# 5_Teensy.net
KiCad netlist of a schematic drawn in Altium Designer
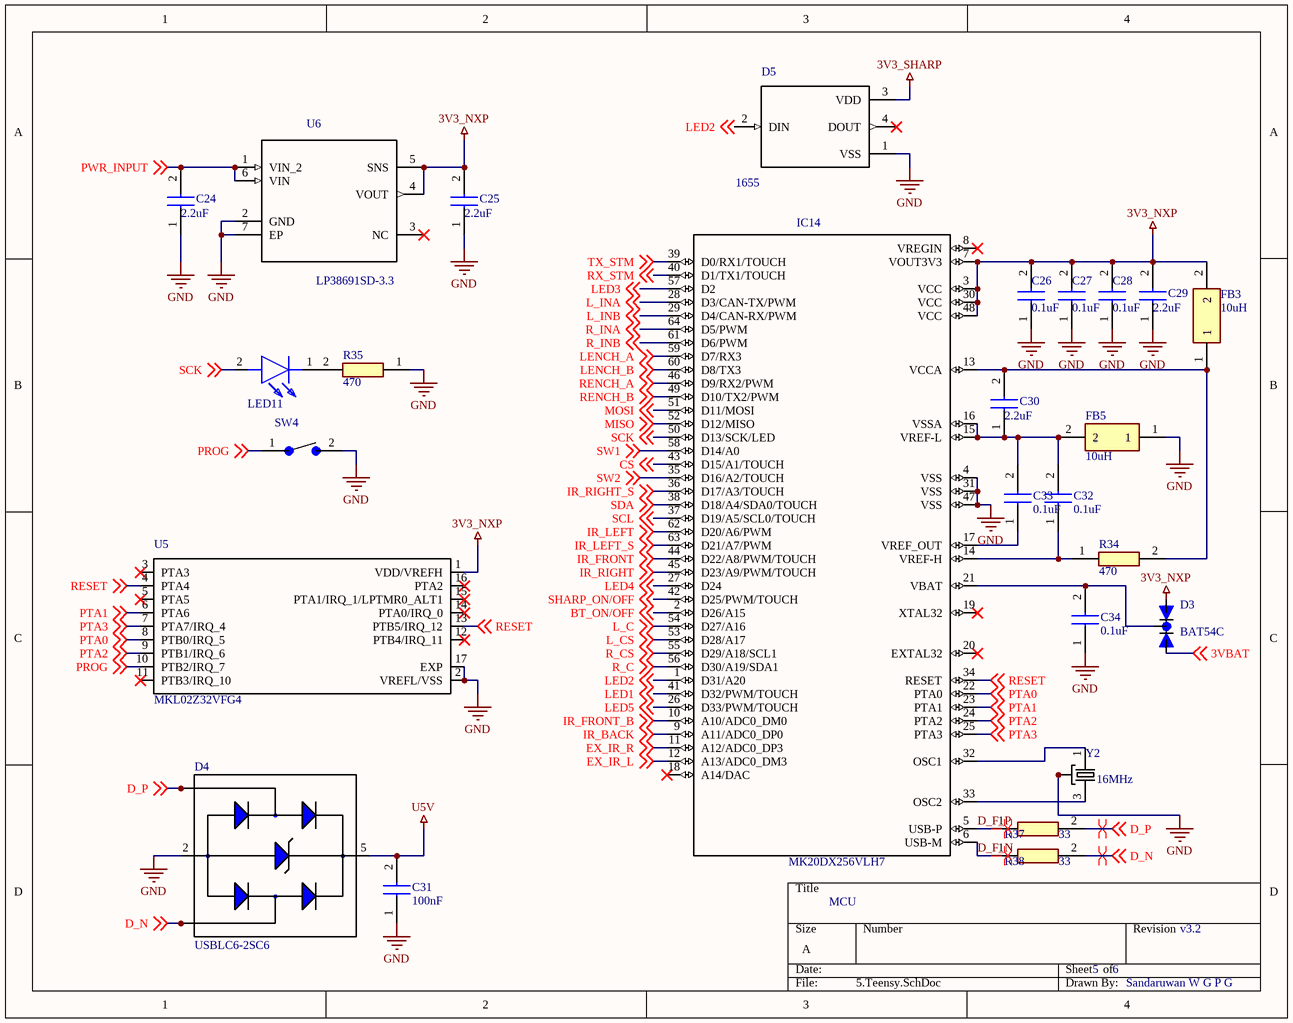
[diagram p0: 5.Teensy.SchDoc]

(export (version "E")
  (design (tool "Eeschema 10.0.6"))
  (components
    (comp (ref "C24")
      (value "2.2uF")
      (footprint "CAPC2012X94N")
      (description "Capacitor")
      (fields
        (field (name "MANUFACTURER_PART_NUMBER") "08055A101JAT2A")
        (field (name "MOUSER PART NUMBER") "581-08055A101J")
      )
      (libsource (lib "micromouse library") (part "08055A101JAT2A"))
    )
    (comp (ref "C25")
      (value "2.2uF")
      (footprint "CAPC2012X94N")
      (description "Capacitor")
      (fields
        (field (name "MANUFACTURER_PART_NUMBER") "08055A101JAT2A")
        (field (name "MOUSER PART NUMBER") "581-08055A101J")
      )
      (libsource (lib "micromouse library") (part "08055A101JAT2A"))
    )
    (comp (ref "C26")
      (value "0.1uF")
      (footprint "*CAPC1608X95N")
      (description "Capacitor")
      (fields (field (name "Comment") "capacitor 0603"))
      (libsource (lib "micromouse library") (part "capacitor 0603"))
    )
    (comp (ref "C27")
      (value "0.1uF")
      (footprint "*CAPC1608X95N")
      (description "Capacitor")
      (fields (field (name "Comment") "capacitor 0603"))
      (libsource (lib "micromouse library") (part "capacitor 0603"))
    )
    (comp (ref "C28")
      (value "0.1uF")
      (footprint "*CAPC1608X95N")
      (description "Capacitor")
      (fields (field (name "Comment") "capacitor 0603"))
      (libsource (lib "micromouse library") (part "capacitor 0603"))
    )
    (comp (ref "C29")
      (value "2.2uF")
      (footprint "CAPC2012X94N")
      (description "Capacitor")
      (fields
        (field (name "MANUFACTURER_PART_NUMBER") "08055A101JAT2A")
        (field (name "MOUSER PART NUMBER") "581-08055A101J")
      )
      (libsource (lib "micromouse library") (part "08055A101JAT2A"))
    )
    (comp (ref "C30")
      (value "2.2uF")
      (footprint "CAPC2012X94N")
      (description "Capacitor")
      (fields
        (field (name "MANUFACTURER_PART_NUMBER") "08055A101JAT2A")
        (field (name "MOUSER PART NUMBER") "581-08055A101J")
      )
      (libsource (lib "micromouse library") (part "08055A101JAT2A"))
    )
    (comp (ref "C31")
      (value "100nF")
      (footprint "*CAPC1608X95N")
      (description "Capacitor")
      (fields (field (name "Comment") "capacitor 0603"))
      (libsource (lib "micromouse library") (part "capacitor 0603"))
    )
    (comp (ref "C32")
      (value "0.1uF")
      (footprint "*CAPC1608X95N")
      (description "Capacitor")
      (fields (field (name "Comment") "capacitor 0603"))
      (libsource (lib "micromouse library") (part "capacitor 0603"))
    )
    (comp (ref "C33")
      (value "0.1uF")
      (footprint "*CAPC1608X95N")
      (description "Capacitor")
      (fields (field (name "Comment") "capacitor 0603"))
      (libsource (lib "micromouse library") (part "capacitor 0603"))
    )
    (comp (ref "C34")
      (value "0.1uF")
      (footprint "*CAPC1608X95N")
      (description "Capacitor")
      (fields (field (name "Comment") "capacitor 0603"))
      (libsource (lib "micromouse library") (part "capacitor 0603"))
    )
    (comp (ref "D3")
      (value "BAT54C")
      (footprint "*SOT23-R")
      (fields (field (name "MF") "ON Semiconductor"))
      (libsource (lib "micromouse library") (part "BAT54C"))
    )
    (comp (ref "D4")
      (value "USBLC6-2SC6")
      (footprint "*SOT95P280X145-6N")
      (description "USBLC6 Series 2 Line 6 V Uni / Bi-Directional ESD Protection - SOT-23-6")
      (fields (field (name "MF") "STMicroelectronics"))
      (libsource (lib "micromouse library") (part "USBLC6-2SC6"))
    )
    (comp (ref "D5")
      (value "1655")
      (footprint "*LED_1655")
      (fields (field (name "DIGI-KEY_PART_NUMBER") "1528-1104-ND") (field (name "MF") "Adafruit"))
      (libsource (lib "micromouse library") (part "1655"))
    )
    (comp (ref "FB3")
      (value "10uH")
      (footprint "BEADC1608X95N")
      (description "Ferrite Bead")
      (fields (field (name "Comment") "inductor 0603"))
      (libsource (lib "") (part "inductor 0603_1"))
    )
    (comp (ref "FB5")
      (value "10uH")
      (footprint "BEADC1608X95N")
      (description "Ferrite Bead")
      (fields (field (name "Comment") "inductor 0603"))
      (libsource (lib "micromouse library") (part "inductor 0603"))
    )
    (comp (ref "IC14")
      (value "MK20DX256VLH7")
      (footprint "QFP50P1200X1200X160-64N")
      (description "Kinetis K20: 72MHz Cortex-M4 Performance MCU, 288KB Flash, 64KB SRAM, Full-Speed USB, 64-LQFP")
      (fields (field (name "MF") "NXP USA"))
      (libsource (lib "micromouse library") (part "MK20DX256VLH7_1"))
    )
    (comp (ref "LED11")
      (value "150080BS75000")
      (footprint "LEDC2012X80N")
      (description "LED")
      (fields
        (field (name "MOUSER PART NUMBER") "710-150080BS75000")
        (field (name "RS PART NUMBER") "8154228P")
      )
      (libsource (lib "micromouse library") (part "150080BS75000"))
    )
    (comp (ref "R34")
      (value "470")
      (footprint "RESC1608X55N")
      (description "Resistor")
      (fields (field (name "Comment") "resistor"))
      (libsource (lib "micromouse library") (part "resistor"))
    )
    (comp (ref "R35")
      (value "470")
      (footprint "RESC1608X55N")
      (description "Resistor")
      (fields (field (name "Comment") "resistor"))
      (libsource (lib "") (part "resistor_1"))
    )
    (comp (ref "R37")
      (value "33")
      (footprint "RESC1608X55N")
      (description "Resistor")
      (fields (field (name "Comment") "resistor"))
      (libsource (lib "micromouse library") (part "resistor"))
    )
    (comp (ref "R38")
      (value "33")
      (footprint "RESC1608X55N")
      (description "Resistor")
      (fields (field (name "Comment") "resistor"))
      (libsource (lib "micromouse library") (part "resistor"))
    )
    (comp (ref "SW4")
      (value "1437566-3")
      (footprint "*TE_FSMSM")
      (description "Switch Tactile OFF _ON_ SPST Rectangular Button Gull Wing 0.05A 12VDC SMD Loose Piece")
      (fields (field (name "MF") "TE Connectivity") (field (name "MP") "FSMSM"))
      (libsource (lib "micromouse library") (part "FSMSM"))
    )
    (comp (ref "U5")
      (value "MKL02Z32VFG4")
      (footprint "*QFN50P300X300X65-17N")
      (description "32 Bit Microcontroller, Kinetis L Series Ultra Low Power, ARM Cortex-M0+, 48 MHz, 32 KB, 4 KB, 16")
      (fields (field (name "MF") "NXP USA"))
      (libsource (lib "micromouse library") (part "MKL02Z32VFG4_1"))
    )
    (comp (ref "U6")
      (value "LP38691SD-3.3")
      (footprint "*DFN300X300X80-7N")
      (description "500mA Low Dropout CMOS Linear Regulators Stable with Ceramic Output Capacitors 6-WSON -40 to 125")
      (fields (field (name "MF") "Texas Instruments"))
      (libsource (lib "micromouse library") (part "LP38691SD-3.3"))
    )
    (comp (ref "Y2")
      (value "16MHz")
      (footprint "*OSCCC320X250X60N")
      (description "Crystal 12.0000mhz 8pf Smd")
      (fields (field (name "MP") "NX3225SA-12.000M-STD-CRS-2") (field (name "MF") "NDK America,"))
      (libsource (lib "micromouse library") (part "NX3225SA-12.000M-STD-CRS-2"))
    )
  )
  (nets
    (net (code "1") (name "/D_F_N") (class "Default")
      (node (ref "IC14") (pin "6") (pinfunction "USB-M_6") (pintype "bidirectional"))
      (node (ref "R38") (pin "1") (pinfunction "1_1") (pintype "passive"))
    )
    (net (code "2") (name "/D_F_P") (class "Default")
      (node (ref "IC14") (pin "5") (pinfunction "USB-P_5") (pintype "bidirectional"))
      (node (ref "R37") (pin "1") (pinfunction "1_1") (pintype "passive"))
    )
    (net (code "3") (name "3V3_NXP") (class "Default")
      (node (ref "C25") (pin "2") (pinfunction "2_2") (pintype "passive"))
      (node (ref "C26") (pin "2") (pinfunction "2_2") (pintype "passive"))
      (node (ref "C27") (pin "2") (pinfunction "2_2") (pintype "passive"))
      (node (ref "C28") (pin "2") (pinfunction "2_2") (pintype "passive"))
      (node (ref "C29") (pin "2") (pinfunction "2_2") (pintype "passive"))
      (node (ref "D3") (pin "2") (pinfunction "A2_2") (pintype "passive"))
      (node (ref "FB3") (pin "2") (pinfunction "2_2") (pintype "passive"))
      (node (ref "IC14") (pin "3") (pinfunction "VCC_3") (pintype "bidirectional"))
      (node (ref "IC14") (pin "30") (pinfunction "VCC_30") (pintype "bidirectional"))
      (node (ref "IC14") (pin "48") (pinfunction "VCC_48") (pintype "bidirectional"))
      (node (ref "IC14") (pin "7") (pinfunction "VOUT3V3_7") (pintype "bidirectional"))
      (node (ref "U5") (pin "1") (pinfunction "VDD/VREFH_1") (pintype "power_in"))
      (node (ref "U6") (pin "4") (pinfunction "VOUT_4") (pintype "output"))
      (node (ref "U6") (pin "5") (pinfunction "SNS_5") (pintype "passive"))
    )
    (net (code "4") (name "3V3_SHARP") (class "Default")
      (node (ref "D5") (pin "3") (pinfunction "VDD_3") (pintype "power_in"))
    )
    (net (code "5") (name "3VBAT") (class "Default")
      (node (ref "D3") (pin "1") (pinfunction "A1_1") (pintype "passive"))
    )
    (net (code "6") (name "BT_ON{slash}OFF") (class "Default")
      (node (ref "IC14") (pin "2") (pinfunction "D26/A15_2") (pintype "bidirectional"))
    )
    (net (code "7") (name "CS") (class "Default")
      (node (ref "IC14") (pin "43") (pinfunction "D15/A1/TOUCH_43") (pintype "bidirectional"))
    )
    (net (code "8") (name "D_N") (class "Default")
      (node (ref "D4") (pin "3") (pinfunction "I/O2_3") (pintype "bidirectional"))
      (node (ref "D4") (pin "4") (pinfunction "I/O2_4") (pintype "bidirectional"))
      (node (ref "R38") (pin "2") (pinfunction "2_2") (pintype "passive"))
    )
    (net (code "9") (name "D_P") (class "Default")
      (node (ref "D4") (pin "1") (pinfunction "I/O1_1") (pintype "bidirectional"))
      (node (ref "D4") (pin "6") (pinfunction "I/O1_6") (pintype "bidirectional"))
      (node (ref "R37") (pin "2") (pinfunction "2_2") (pintype "passive"))
    )
    (net (code "10") (name "EX_IR_L") (class "Default")
      (node (ref "IC14") (pin "12") (pinfunction "A13/ADC0_DM3_12") (pintype "bidirectional"))
    )
    (net (code "11") (name "EX_IR_R") (class "Default")
      (node (ref "IC14") (pin "11") (pinfunction "A12/ADC0_DP3_11") (pintype "bidirectional"))
    )
    (net (code "12") (name "GND") (class "Default")
      (node (ref "C24") (pin "1") (pinfunction "1_1") (pintype "passive"))
      (node (ref "C25") (pin "1") (pinfunction "1_1") (pintype "passive"))
      (node (ref "C26") (pin "1") (pinfunction "1_1") (pintype "passive"))
      (node (ref "C27") (pin "1") (pinfunction "1_1") (pintype "passive"))
      (node (ref "C28") (pin "1") (pinfunction "1_1") (pintype "passive"))
      (node (ref "C29") (pin "1") (pinfunction "1_1") (pintype "passive"))
      (node (ref "C31") (pin "1") (pinfunction "1_1") (pintype "passive"))
      (node (ref "C34") (pin "1") (pinfunction "1_1") (pintype "passive"))
      (node (ref "D4") (pin "2") (pinfunction "GND_2") (pintype "power_in"))
      (node (ref "D5") (pin "1") (pinfunction "VSS_1") (pintype "power_in"))
      (node (ref "FB5") (pin "1") (pinfunction "1_1") (pintype "passive"))
      (node (ref "IC14") (pin "31") (pinfunction "VSS_31") (pintype "bidirectional"))
      (node (ref "IC14") (pin "4") (pinfunction "VSS_4") (pintype "bidirectional"))
      (node (ref "IC14") (pin "47") (pinfunction "VSS_47") (pintype "bidirectional"))
      (node (ref "R35") (pin "1") (pinfunction "1_1") (pintype "passive"))
      (node (ref "SW4") (pin "2") (pinfunction "2_2") (pintype "passive"))
      (node (ref "U5") (pin "17") (pinfunction "EXP_17") (pintype "power_in"))
      (node (ref "U5") (pin "2") (pinfunction "VREFL/VSS_2") (pintype "power_in"))
      (node (ref "U6") (pin "2") (pinfunction "GND_2") (pintype "passive"))
      (node (ref "U6") (pin "7") (pinfunction "EP_7") (pintype "passive"))
      (node (ref "Y2") (pin "2") (pinfunction "GND_2") (pintype "passive"))
      (node (ref "Y2") (pin "4") (pinfunction "GND_4") (pintype "passive"))
    )
    (net (code "13") (name "IR_BACK") (class "Default")
      (node (ref "IC14") (pin "9") (pinfunction "A11/ADC0_DP0_9") (pintype "bidirectional"))
    )
    (net (code "14") (name "IR_FRONT") (class "Default")
      (node (ref "IC14") (pin "44") (pinfunction "D22/A8/PWM/TOUCH_44") (pintype "bidirectional"))
    )
    (net (code "15") (name "IR_FRONT_B") (class "Default")
      (node (ref "IC14") (pin "10") (pinfunction "A10/ADC0_DM0_10") (pintype "bidirectional"))
    )
    (net (code "16") (name "IR_LEFT") (class "Default")
      (node (ref "IC14") (pin "62") (pinfunction "D20/A6/PWM_62") (pintype "bidirectional"))
    )
    (net (code "17") (name "IR_LEFT_S") (class "Default")
      (node (ref "IC14") (pin "63") (pinfunction "D21/A7/PWM_63") (pintype "bidirectional"))
    )
    (net (code "18") (name "IR_RIGHT") (class "Default")
      (node (ref "IC14") (pin "45") (pinfunction "D23/A9/PWM/TOUCH_45") (pintype "bidirectional"))
    )
    (net (code "19") (name "IR_RIGHT_S") (class "Default")
      (node (ref "IC14") (pin "36") (pinfunction "D17/A3/TOUCH_36") (pintype "bidirectional"))
    )
    (net (code "20") (name "LED1") (class "Default")
      (node (ref "IC14") (pin "41") (pinfunction "D32/PWM/TOUCH_41") (pintype "bidirectional"))
    )
    (net (code "21") (name "LED2") (class "Default")
      (node (ref "D5") (pin "2") (pinfunction "DIN_2") (pintype "input"))
      (node (ref "IC14") (pin "1") (pinfunction "D31/A20_1") (pintype "bidirectional"))
    )
    (net (code "22") (name "LED3") (class "Default")
      (node (ref "IC14") (pin "57") (pinfunction "D2_57") (pintype "bidirectional"))
    )
    (net (code "23") (name "LED4") (class "Default")
      (node (ref "IC14") (pin "27") (pinfunction "D24_27") (pintype "bidirectional"))
    )
    (net (code "24") (name "LED5") (class "Default")
      (node (ref "IC14") (pin "26") (pinfunction "D33/PWM/TOUCH_26") (pintype "bidirectional"))
    )
    (net (code "25") (name "LENCH_A") (class "Default")
      (node (ref "IC14") (pin "59") (pinfunction "D7/RX3_59") (pintype "bidirectional"))
    )
    (net (code "26") (name "LENCH_B") (class "Default")
      (node (ref "IC14") (pin "60") (pinfunction "D8/TX3_60") (pintype "bidirectional"))
    )
    (net (code "27") (name "L_C") (class "Default")
      (node (ref "IC14") (pin "54") (pinfunction "D27/A16_54") (pintype "bidirectional"))
    )
    (net (code "28") (name "L_CS") (class "Default")
      (node (ref "IC14") (pin "53") (pinfunction "D28/A17_53") (pintype "bidirectional"))
    )
    (net (code "29") (name "L_INA") (class "Default")
      (node (ref "IC14") (pin "28") (pinfunction "D3/CAN-TX/PWM_28") (pintype "bidirectional"))
    )
    (net (code "30") (name "L_INB") (class "Default")
      (node (ref "IC14") (pin "29") (pinfunction "D4/CAN-RX/PWM_29") (pintype "bidirectional"))
    )
    (net (code "31") (name "MISO") (class "Default")
      (node (ref "IC14") (pin "52") (pinfunction "D12/MISO_52") (pintype "bidirectional"))
    )
    (net (code "32") (name "MOSI") (class "Default")
      (node (ref "IC14") (pin "51") (pinfunction "D11/MOSI_51") (pintype "bidirectional"))
    )
    (net (code "33") (name "Net-(D3-C)") (class "Default")
      (node (ref "C34") (pin "2") (pinfunction "2_2") (pintype "passive"))
      (node (ref "D3") (pin "3") (pinfunction "C_3") (pintype "passive"))
      (node (ref "IC14") (pin "21") (pinfunction "VBAT_21") (pintype "bidirectional"))
    )
    (net (code "34") (name "Net-(IC14-OSC1)") (class "Default")
      (node (ref "IC14") (pin "32") (pinfunction "OSC1_32") (pintype "bidirectional"))
      (node (ref "Y2") (pin "1") (pinfunction "1_1") (pintype "passive"))
    )
    (net (code "35") (name "Net-(IC14-OSC2)") (class "Default")
      (node (ref "IC14") (pin "33") (pinfunction "OSC2_33") (pintype "bidirectional"))
      (node (ref "Y2") (pin "3") (pinfunction "3_3") (pintype "passive"))
    )
    (net (code "36") (name "Net-(IC14-VCCA)") (class "Default")
      (node (ref "C30") (pin "2") (pinfunction "2_2") (pintype "passive"))
      (node (ref "FB3") (pin "1") (pinfunction "1_1") (pintype "passive"))
      (node (ref "IC14") (pin "13") (pinfunction "VCCA_13") (pintype "bidirectional"))
      (node (ref "R34") (pin "2") (pinfunction "2_2") (pintype "passive"))
    )
    (net (code "37") (name "Net-(IC14-VREF-H)") (class "Default")
      (node (ref "C32") (pin "1") (pinfunction "1_1") (pintype "passive"))
      (node (ref "IC14") (pin "14") (pinfunction "VREF-H_14") (pintype "bidirectional"))
      (node (ref "R34") (pin "1") (pinfunction "1_1") (pintype "passive"))
    )
    (net (code "38") (name "Net-(IC14-VREF-L)") (class "Default")
      (node (ref "C30") (pin "1") (pinfunction "1_1") (pintype "passive"))
      (node (ref "C32") (pin "2") (pinfunction "2_2") (pintype "passive"))
      (node (ref "C33") (pin "2") (pinfunction "2_2") (pintype "passive"))
      (node (ref "FB5") (pin "2") (pinfunction "2_2") (pintype "passive"))
      (node (ref "IC14") (pin "15") (pinfunction "VREF-L_15") (pintype "bidirectional"))
      (node (ref "IC14") (pin "16") (pinfunction "VSSA_16") (pintype "bidirectional"))
    )
    (net (code "39") (name "Net-(IC14-VREF_OUT)") (class "Default")
      (node (ref "C33") (pin "1") (pinfunction "1_1") (pintype "passive"))
      (node (ref "IC14") (pin "17") (pinfunction "VREF_OUT_17") (pintype "bidirectional"))
    )
    (net (code "40") (name "Net-(LED11-K)") (class "Default")
      (node (ref "LED11") (pin "1") (pinfunction "K_1") (pintype "passive"))
      (node (ref "R35") (pin "2") (pinfunction "2_2") (pintype "passive"))
    )
    (net (code "41") (name "PROG") (class "Default")
      (node (ref "SW4") (pin "1") (pinfunction "1_1") (pintype "passive"))
      (node (ref "U5") (pin "10") (pinfunction "PTB2/IRQ_7_10") (pintype "bidirectional"))
    )
    (net (code "42") (name "PTA0") (class "Default")
      (node (ref "IC14") (pin "22") (pinfunction "PTA0_22") (pintype "bidirectional"))
      (node (ref "U5") (pin "8") (pinfunction "PTB0/IRQ_5_8") (pintype "bidirectional"))
    )
    (net (code "43") (name "PTA1") (class "Default")
      (node (ref "IC14") (pin "23") (pinfunction "PTA1_23") (pintype "bidirectional"))
      (node (ref "U5") (pin "6") (pinfunction "PTA6_6") (pintype "bidirectional"))
    )
    (net (code "44") (name "PTA2") (class "Default")
      (node (ref "IC14") (pin "24") (pinfunction "PTA2_24") (pintype "bidirectional"))
      (node (ref "U5") (pin "9") (pinfunction "PTB1/IRQ_6_9") (pintype "bidirectional"))
    )
    (net (code "45") (name "PTA3") (class "Default")
      (node (ref "IC14") (pin "25") (pinfunction "PTA3_25") (pintype "bidirectional"))
      (node (ref "U5") (pin "7") (pinfunction "PTA7/IRQ_4_7") (pintype "bidirectional"))
    )
    (net (code "46") (name "PWR_INPUT") (class "Default")
      (node (ref "C24") (pin "2") (pinfunction "2_2") (pintype "passive"))
      (node (ref "U6") (pin "1") (pinfunction "VIN_2_1") (pintype "input"))
      (node (ref "U6") (pin "6") (pinfunction "VIN_6") (pintype "input"))
    )
    (net (code "47") (name "RENCH_A") (class "Default")
      (node (ref "IC14") (pin "46") (pinfunction "D9/RX2/PWM_46") (pintype "bidirectional"))
    )
    (net (code "48") (name "RENCH_B") (class "Default")
      (node (ref "IC14") (pin "49") (pinfunction "D10/TX2/PWM_49") (pintype "bidirectional"))
    )
    (net (code "49") (name "RESET") (class "Default")
      (node (ref "IC14") (pin "34") (pinfunction "RESET_34") (pintype "bidirectional"))
      (node (ref "U5") (pin "13") (pinfunction "PTB5/IRQ_12_13") (pintype "bidirectional"))
      (node (ref "U5") (pin "4") (pinfunction "PTA4_4") (pintype "bidirectional"))
    )
    (net (code "50") (name "RX_STM") (class "Default")
      (node (ref "IC14") (pin "40") (pinfunction "D1/TX1/TOUCH_40") (pintype "bidirectional"))
    )
    (net (code "51") (name "R_C") (class "Default")
      (node (ref "IC14") (pin "56") (pinfunction "D30/A19/SDA1_56") (pintype "bidirectional"))
    )
    (net (code "52") (name "R_CS") (class "Default")
      (node (ref "IC14") (pin "55") (pinfunction "D29/A18/SCL1_55") (pintype "bidirectional"))
    )
    (net (code "53") (name "R_INA") (class "Default")
      (node (ref "IC14") (pin "64") (pinfunction "D5/PWM_64") (pintype "bidirectional"))
    )
    (net (code "54") (name "R_INB") (class "Default")
      (node (ref "IC14") (pin "61") (pinfunction "D6/PWM_61") (pintype "bidirectional"))
    )
    (net (code "55") (name "SCK") (class "Default")
      (node (ref "IC14") (pin "50") (pinfunction "D13/SCK/LED_50") (pintype "bidirectional"))
      (node (ref "LED11") (pin "2") (pinfunction "A_2") (pintype "passive"))
    )
    (net (code "56") (name "SCL") (class "Default")
      (node (ref "IC14") (pin "37") (pinfunction "D19/A5/SCL0/TOUCH_37") (pintype "bidirectional"))
    )
    (net (code "57") (name "SDA") (class "Default")
      (node (ref "IC14") (pin "38") (pinfunction "D18/A4/SDA0/TOUCH_38") (pintype "bidirectional"))
    )
    (net (code "58") (name "SHARP_ON{slash}OFF") (class "Default")
      (node (ref "IC14") (pin "42") (pinfunction "D25/PWM/TOUCH_42") (pintype "bidirectional"))
    )
    (net (code "59") (name "SW1") (class "Default")
      (node (ref "IC14") (pin "58") (pinfunction "D14/A0_58") (pintype "bidirectional"))
    )
    (net (code "60") (name "SW2") (class "Default")
      (node (ref "IC14") (pin "35") (pinfunction "D16/A2/TOUCH_35") (pintype "bidirectional"))
    )
    (net (code "61") (name "TX_STM") (class "Default")
      (node (ref "IC14") (pin "39") (pinfunction "D0/RX1/TOUCH_39") (pintype "bidirectional"))
    )
    (net (code "62") (name "U5V") (class "Default")
      (node (ref "C31") (pin "2") (pinfunction "2_2") (pintype "passive"))
      (node (ref "D4") (pin "5") (pinfunction "VBUS_5") (pintype "power_in"))
    )
    (net (code "63") (name "unconnected-(D5-DOUT-Pad4)") (class "Default")
      (node (ref "D5") (pin "4") (pinfunction "DOUT_4") (pintype "output+no_connect"))
    )
    (net (code "64") (name "unconnected-(IC14-A14{slash}DAC-Pad18)") (class "Default")
      (node (ref "IC14") (pin "18") (pinfunction "A14/DAC_18") (pintype "bidirectional+no_connect"))
    )
    (net (code "65") (name "unconnected-(IC14-EXTAL32-Pad20)") (class "Default")
      (node (ref "IC14") (pin "20") (pinfunction "EXTAL32_20") (pintype "bidirectional+no_connect"))
    )
    (net (code "66") (name "unconnected-(IC14-VREGIN-Pad8)") (class "Default")
      (node (ref "IC14") (pin "8") (pinfunction "VREGIN_8") (pintype "bidirectional+no_connect"))
    )
    (net (code "67") (name "unconnected-(IC14-XTAL32-Pad19)") (class "Default")
      (node (ref "IC14") (pin "19") (pinfunction "XTAL32_19") (pintype "bidirectional+no_connect"))
    )
    (net (code "68") (name "unconnected-(U5-PTA0{slash}IRQ_0-Pad14)") (class "Default")
      (node (ref "U5") (pin "14") (pinfunction "PTA0/IRQ_0_14") (pintype "bidirectional+no_connect"))
    )
    (net (code "69") (name "unconnected-(U5-PTA1{slash}IRQ_1{slash}LPTMR0_ALT1-Pad15)") (class "Default")
      (node (ref "U5") (pin "15") (pinfunction "PTA1/IRQ_1/LPTMR0_ALT1_15") (pintype "bidirectional+no_connect"))
    )
    (net (code "70") (name "unconnected-(U5-PTA2-Pad16)") (class "Default")
      (node (ref "U5") (pin "16") (pinfunction "PTA2_16") (pintype "bidirectional+no_connect"))
    )
    (net (code "71") (name "unconnected-(U5-PTA3-Pad3)") (class "Default")
      (node (ref "U5") (pin "3") (pinfunction "PTA3_3") (pintype "bidirectional+no_connect"))
    )
    (net (code "72") (name "unconnected-(U5-PTA5-Pad5)") (class "Default")
      (node (ref "U5") (pin "5") (pinfunction "PTA5_5") (pintype "bidirectional+no_connect"))
    )
    (net (code "73") (name "unconnected-(U5-PTB3{slash}IRQ_10-Pad11)") (class "Default")
      (node (ref "U5") (pin "11") (pinfunction "PTB3/IRQ_10_11") (pintype "bidirectional+no_connect"))
    )
    (net (code "74") (name "unconnected-(U5-PTB4{slash}IRQ_11-Pad12)") (class "Default")
      (node (ref "U5") (pin "12") (pinfunction "PTB4/IRQ_11_12") (pintype "bidirectional+no_connect"))
    )
    (net (code "75") (name "unconnected-(U6-NC-Pad3)") (class "Default")
      (node (ref "U6") (pin "3") (pinfunction "NC_3") (pintype "passive+no_connect"))
    )
  )
)
